# 153-01C_Mode_X_LPT_adapter.net
KiCad netlist of a schematic drawn in EAGLE
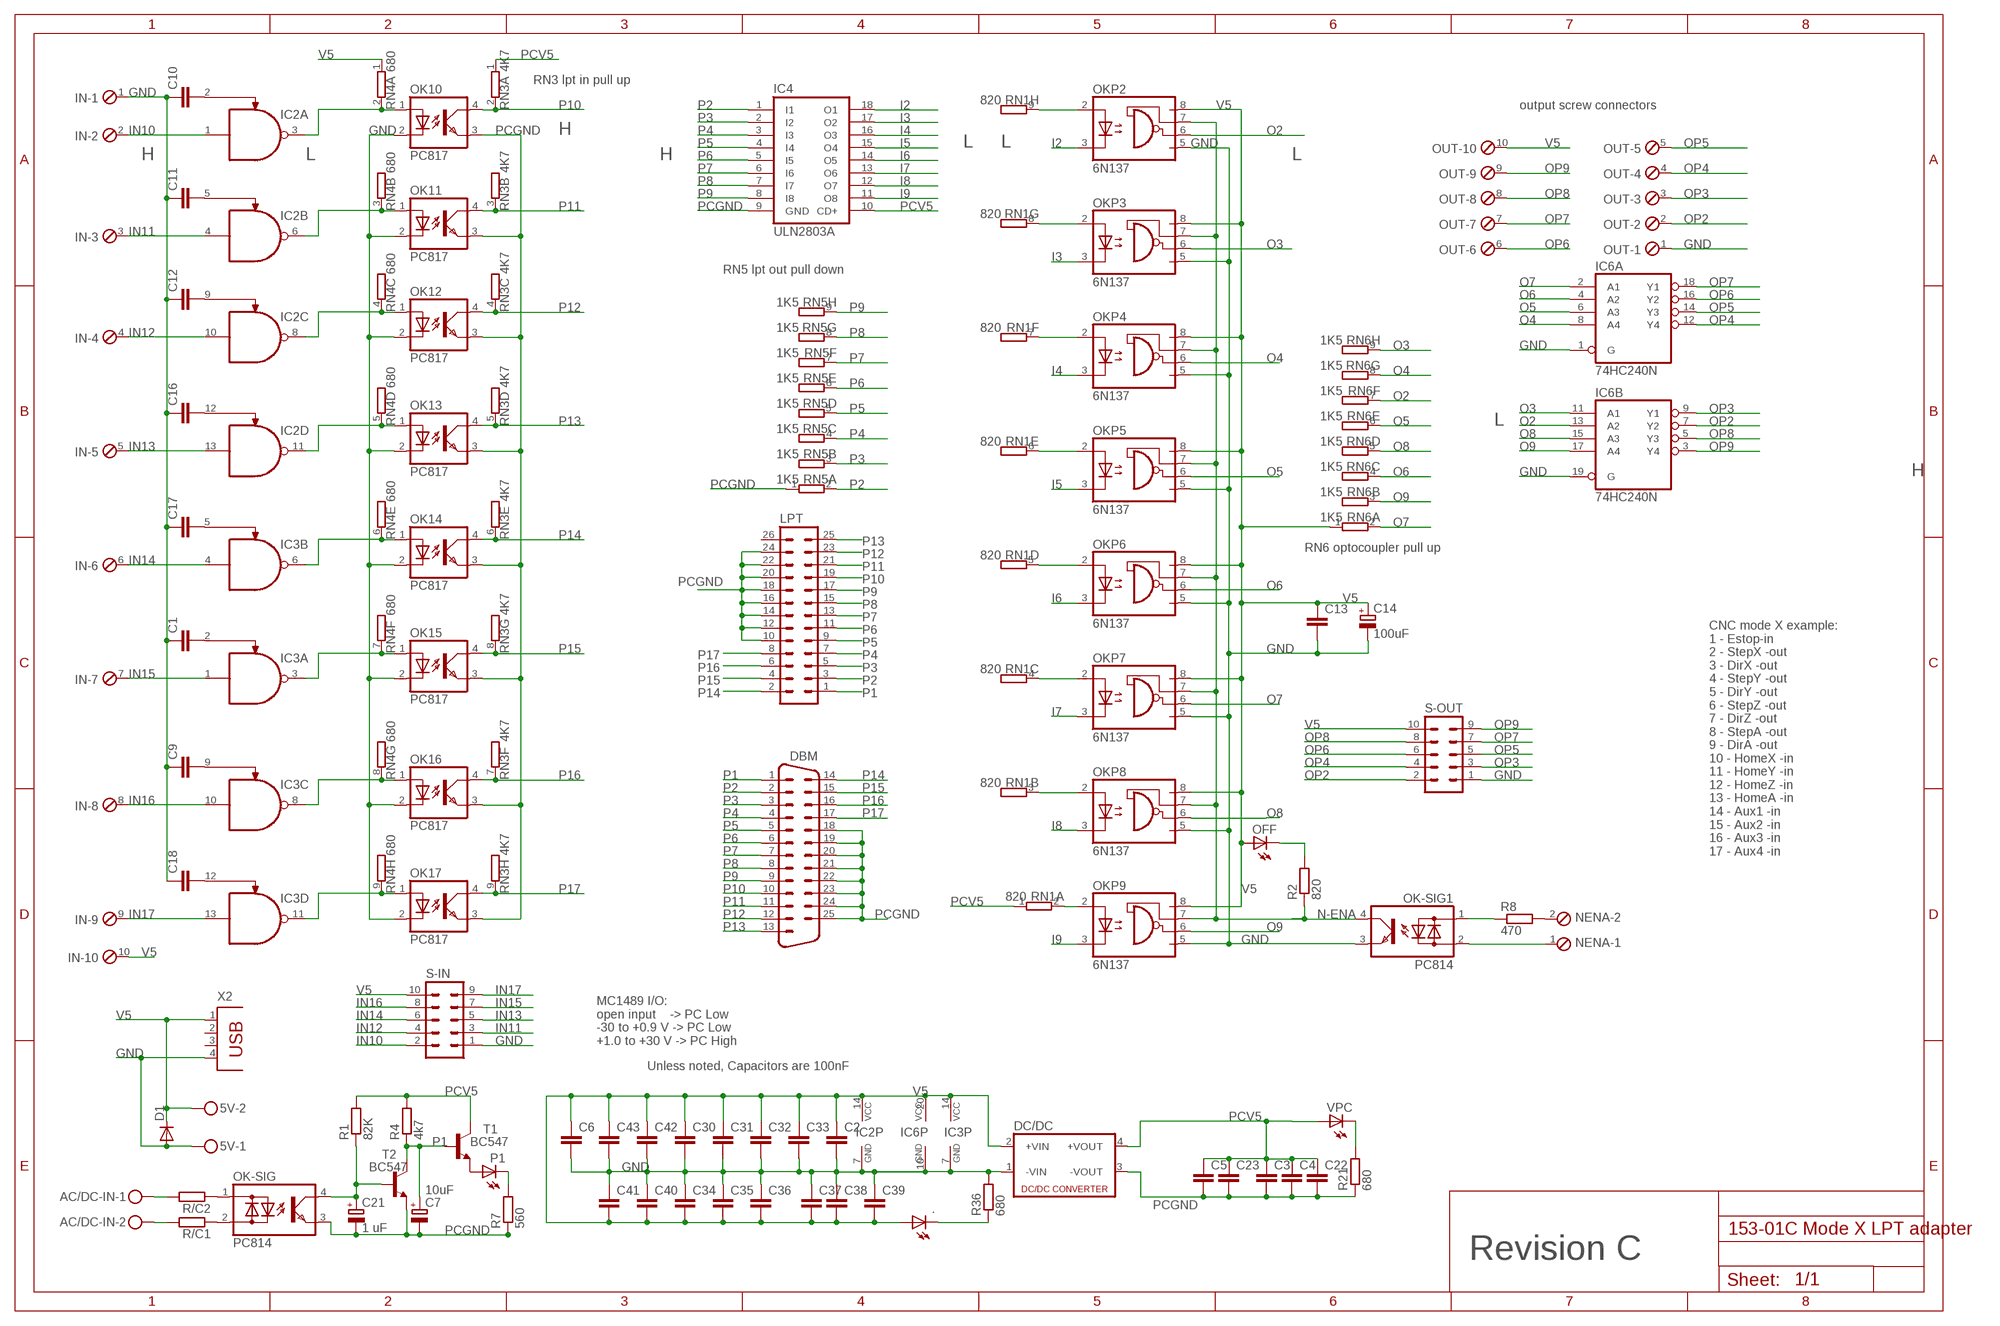
[diagram p0: schematic, sheet 1]

(export (version "E")
  (design (tool "Eeschema 10.0.6"))
  (components
    (comp (ref ".")
      (value "LED3MM")
      (footprint "eagle-import:LED3MM")
      (libsource (lib "eagle-import") (part "LED3MM"))
    )
    (comp (ref "5V")
      (value "MKDSN1,5/2-5,08")
      (footprint "eagle-import:MKDSN1,5_2-5,08")
      (libsource (lib "eagle-import") (part "MKDSN1,5/2-5,08"))
    )
    (comp (ref "AC/DC-IN")
      (value "MKDSN1,5/2-5,08")
      (footprint "eagle-import:MKDSN1,5_2-5,08")
      (libsource (lib "eagle-import") (part "MKDSN1,5/2-5,08"))
    )
    (comp (ref "C1")
      (value "C-EU025-024X044")
      (footprint "eagle-import:C025-024X044")
      (libsource (lib "eagle-import") (part "C-EU025-024X044"))
    )
    (comp (ref "C2")
      (value "C-EU025-024X044")
      (footprint "eagle-import:C025-024X044")
      (libsource (lib "eagle-import") (part "C-EU025-024X044"))
    )
    (comp (ref "C3")
      (value "C-EU025-024X044")
      (footprint "eagle-import:C025-024X044")
      (libsource (lib "eagle-import") (part "C-EU025-024X044"))
    )
    (comp (ref "C4")
      (value "C-EU025-024X044")
      (footprint "eagle-import:C025-024X044")
      (libsource (lib "eagle-import") (part "C-EU025-024X044"))
    )
    (comp (ref "C5")
      (value "C-EU025-024X044")
      (footprint "eagle-import:C025-024X044")
      (libsource (lib "eagle-import") (part "C-EU025-024X044"))
    )
    (comp (ref "C6")
      (value "C-EU025-024X044")
      (footprint "eagle-import:C025-024X044")
      (libsource (lib "eagle-import") (part "C-EU025-024X044"))
    )
    (comp (ref "C7")
      (value "10uF")
      (footprint "eagle-import:E5-6")
      (libsource (lib "eagle-import") (part "CPOL-EUE5-6"))
    )
    (comp (ref "C9")
      (value "C-EU025-024X044")
      (footprint "eagle-import:C025-024X044")
      (libsource (lib "eagle-import") (part "C-EU025-024X044"))
    )
    (comp (ref "C10")
      (value "C-EU025-024X044")
      (footprint "eagle-import:C025-024X044")
      (libsource (lib "eagle-import") (part "C-EU025-024X044"))
    )
    (comp (ref "C11")
      (value "C-EU025-024X044")
      (footprint "eagle-import:C025-024X044")
      (libsource (lib "eagle-import") (part "C-EU025-024X044"))
    )
    (comp (ref "C12")
      (value "C-EU025-024X044")
      (footprint "eagle-import:C025-024X044")
      (libsource (lib "eagle-import") (part "C-EU025-024X044"))
    )
    (comp (ref "C13")
      (value "C-EU025-024X044")
      (footprint "eagle-import:C025-024X044")
      (libsource (lib "eagle-import") (part "C-EU025-024X044"))
    )
    (comp (ref "C14")
      (value "100uF")
      (footprint "eagle-import:E3,5-8")
      (libsource (lib "eagle-import") (part "CPOL-EUE3.5-8"))
    )
    (comp (ref "C16")
      (value "C-EU025-024X044")
      (footprint "eagle-import:C025-024X044")
      (libsource (lib "eagle-import") (part "C-EU025-024X044"))
    )
    (comp (ref "C17")
      (value "C-EU025-024X044")
      (footprint "eagle-import:C025-024X044")
      (libsource (lib "eagle-import") (part "C-EU025-024X044"))
    )
    (comp (ref "C18")
      (value "C-EU025-024X044")
      (footprint "eagle-import:C025-024X044")
      (libsource (lib "eagle-import") (part "C-EU025-024X044"))
    )
    (comp (ref "C21")
      (value "1 uF")
      (footprint "eagle-import:E2,5-6")
      (libsource (lib "eagle-import") (part "CPOL-EUE2.5-6"))
    )
    (comp (ref "C22")
      (value "C-EU025-024X044")
      (footprint "eagle-import:C025-024X044")
      (libsource (lib "eagle-import") (part "C-EU025-024X044"))
    )
    (comp (ref "C23")
      (value "C-EU025-024X044")
      (footprint "eagle-import:C025-024X044")
      (libsource (lib "eagle-import") (part "C-EU025-024X044"))
    )
    (comp (ref "C30")
      (value "C-EU025-024X044")
      (footprint "eagle-import:C025-024X044")
      (libsource (lib "eagle-import") (part "C-EU025-024X044"))
    )
    (comp (ref "C31")
      (value "C-EU025-024X044")
      (footprint "eagle-import:C025-024X044")
      (libsource (lib "eagle-import") (part "C-EU025-024X044"))
    )
    (comp (ref "C32")
      (value "C-EU025-024X044")
      (footprint "eagle-import:C025-024X044")
      (libsource (lib "eagle-import") (part "C-EU025-024X044"))
    )
    (comp (ref "C33")
      (value "C-EU025-024X044")
      (footprint "eagle-import:C025-024X044")
      (libsource (lib "eagle-import") (part "C-EU025-024X044"))
    )
    (comp (ref "C34")
      (value "C-EU025-024X044")
      (footprint "eagle-import:C025-024X044")
      (libsource (lib "eagle-import") (part "C-EU025-024X044"))
    )
    (comp (ref "C35")
      (value "C-EU025-024X044")
      (footprint "eagle-import:C025-024X044")
      (libsource (lib "eagle-import") (part "C-EU025-024X044"))
    )
    (comp (ref "C36")
      (value "C-EU025-024X044")
      (footprint "eagle-import:C025-024X044")
      (libsource (lib "eagle-import") (part "C-EU025-024X044"))
    )
    (comp (ref "C37")
      (value "C-EU025-024X044")
      (footprint "eagle-import:C025-024X044")
      (libsource (lib "eagle-import") (part "C-EU025-024X044"))
    )
    (comp (ref "C38")
      (value "C-EU025-024X044")
      (footprint "eagle-import:C025-024X044")
      (libsource (lib "eagle-import") (part "C-EU025-024X044"))
    )
    (comp (ref "C39")
      (value "C-EU025-024X044")
      (footprint "eagle-import:C025-024X044")
      (libsource (lib "eagle-import") (part "C-EU025-024X044"))
    )
    (comp (ref "C40")
      (value "C-EU025-024X044")
      (footprint "eagle-import:C025-024X044")
      (libsource (lib "eagle-import") (part "C-EU025-024X044"))
    )
    (comp (ref "C41")
      (value "C-EU025-024X044")
      (footprint "eagle-import:C025-024X044")
      (libsource (lib "eagle-import") (part "C-EU025-024X044"))
    )
    (comp (ref "C42")
      (value "C-EU025-024X044")
      (footprint "eagle-import:C025-024X044")
      (libsource (lib "eagle-import") (part "C-EU025-024X044"))
    )
    (comp (ref "C43")
      (value "C-EU025-024X044")
      (footprint "eagle-import:C025-024X044")
      (libsource (lib "eagle-import") (part "C-EU025-024X044"))
    )
    (comp (ref "D1")
      (value "1N4148DO35-10")
      (footprint "eagle-import:DO35-10")
      (libsource (lib "eagle-import") (part "1N4148DO35-10"))
    )
    (comp (ref "DBM")
      (value "M25HP")
      (footprint "eagle-import:M25HP")
      (libsource (lib "eagle-import") (part "M25HP"))
    )
    (comp (ref "DC/DC")
      (value "VA-1205S")
      (footprint "eagle-import:4SIL")
      (libsource (lib "eagle-import") (part "VA-?S1205"))
    )
    (comp (ref "IC2")
      (value "MC1489DIP")
      (footprint "eagle-import:DIL14")
      (libsource (lib "eagle-import") (part "MC1489DIP"))
    )
    (comp (ref "IC3")
      (value "MC1489DIP")
      (footprint "eagle-import:DIL14")
      (libsource (lib "eagle-import") (part "MC1489DIP"))
    )
    (comp (ref "IC4")
      (value "ULN2803A")
      (footprint "eagle-import:DIL18")
      (libsource (lib "eagle-import") (part "ULN2803A"))
    )
    (comp (ref "IC6")
      (value "74HC240N")
      (footprint "eagle-import:DIL20")
      (libsource (lib "eagle-import") (part "74240NHC"))
    )
    (comp (ref "IN")
      (value "MPT10")
      (footprint "eagle-import:10POL254")
      (libsource (lib "eagle-import") (part "MPT10"))
    )
    (comp (ref "LPT")
      (value "ML26")
      (footprint "eagle-import:ML26")
      (libsource (lib "eagle-import") (part "ML26"))
    )
    (comp (ref "NENA")
      (value "MPT2")
      (footprint "eagle-import:2POL254")
      (libsource (lib "eagle-import") (part "MPT2"))
    )
    (comp (ref "OFF")
      (value "LED3MM")
      (footprint "eagle-import:LED3MM")
      (libsource (lib "eagle-import") (part "LED3MM"))
    )
    (comp (ref "OK-SIG")
      (value "PC814")
      (footprint "eagle-import:DIL04")
      (libsource (lib "eagle-import") (part "PC814"))
    )
    (comp (ref "OK-SIG1")
      (value "PC814")
      (footprint "eagle-import:DIL04")
      (libsource (lib "eagle-import") (part "PC814"))
    )
    (comp (ref "OK10")
      (value "PC817")
      (footprint "eagle-import:DIL04")
      (fields (field (name "MPN") "PC817X4J000F"))
      (libsource (lib "eagle-import") (part "PC817"))
    )
    (comp (ref "OK11")
      (value "PC817")
      (footprint "eagle-import:DIL04")
      (fields (field (name "MPN") "PC817X4J000F"))
      (libsource (lib "eagle-import") (part "PC817"))
    )
    (comp (ref "OK12")
      (value "PC817")
      (footprint "eagle-import:DIL04")
      (fields (field (name "MPN") "PC817X4J000F"))
      (libsource (lib "eagle-import") (part "PC817"))
    )
    (comp (ref "OK13")
      (value "PC817")
      (footprint "eagle-import:DIL04")
      (fields (field (name "MPN") "PC817X4J000F"))
      (libsource (lib "eagle-import") (part "PC817"))
    )
    (comp (ref "OK14")
      (value "PC817")
      (footprint "eagle-import:DIL04")
      (fields (field (name "MPN") "PC817X4J000F"))
      (libsource (lib "eagle-import") (part "PC817"))
    )
    (comp (ref "OK15")
      (value "PC817")
      (footprint "eagle-import:DIL04")
      (fields (field (name "MPN") "PC817X4J000F"))
      (libsource (lib "eagle-import") (part "PC817"))
    )
    (comp (ref "OK16")
      (value "PC817")
      (footprint "eagle-import:DIL04")
      (fields (field (name "MPN") "PC817X4J000F"))
      (libsource (lib "eagle-import") (part "PC817"))
    )
    (comp (ref "OK17")
      (value "PC817")
      (footprint "eagle-import:DIL04")
      (fields (field (name "MPN") "PC817X4J000F"))
      (libsource (lib "eagle-import") (part "PC817"))
    )
    (comp (ref "OKP2")
      (value "6N137")
      (footprint "eagle-import:DIL08")
      (libsource (lib "eagle-import") (part "6N137"))
    )
    (comp (ref "OKP3")
      (value "6N137")
      (footprint "eagle-import:DIL08")
      (libsource (lib "eagle-import") (part "6N137"))
    )
    (comp (ref "OKP4")
      (value "6N137")
      (footprint "eagle-import:DIL08")
      (libsource (lib "eagle-import") (part "6N137"))
    )
    (comp (ref "OKP5")
      (value "6N137")
      (footprint "eagle-import:DIL08")
      (libsource (lib "eagle-import") (part "6N137"))
    )
    (comp (ref "OKP6")
      (value "6N137")
      (footprint "eagle-import:DIL08")
      (libsource (lib "eagle-import") (part "6N137"))
    )
    (comp (ref "OKP7")
      (value "6N137")
      (footprint "eagle-import:DIL08")
      (libsource (lib "eagle-import") (part "6N137"))
    )
    (comp (ref "OKP8")
      (value "6N137")
      (footprint "eagle-import:DIL08")
      (libsource (lib "eagle-import") (part "6N137"))
    )
    (comp (ref "OKP9")
      (value "6N137")
      (footprint "eagle-import:DIL08")
      (libsource (lib "eagle-import") (part "6N137"))
    )
    (comp (ref "OUT")
      (value "MPT10")
      (footprint "eagle-import:10POL254")
      (libsource (lib "eagle-import") (part "MPT10"))
    )
    (comp (ref "P1")
      (value "LED3MM")
      (footprint "eagle-import:LED3MM")
      (libsource (lib "eagle-import") (part "LED3MM"))
    )
    (comp (ref "R/C1")
      (value "R-EU_0309/10")
      (footprint "eagle-import:0309_10")
      (libsource (lib "eagle-import") (part "R-EU_0309/10"))
    )
    (comp (ref "R/C2")
      (value "R-EU_0309/10")
      (footprint "eagle-import:0309_10")
      (libsource (lib "eagle-import") (part "R-EU_0309/10"))
    )
    (comp (ref "R1")
      (value "82K")
      (footprint "eagle-import:0207_10")
      (libsource (lib "eagle-import") (part "R-EU_0207/10"))
    )
    (comp (ref "R2")
      (value "820")
      (footprint "eagle-import:0207_10")
      (libsource (lib "eagle-import") (part "R-EU_0207/10"))
    )
    (comp (ref "R4")
      (value "4k7")
      (footprint "eagle-import:0207_10")
      (libsource (lib "eagle-import") (part "R-EU_0207/10"))
    )
    (comp (ref "R7")
      (value "560")
      (footprint "eagle-import:0207_10")
      (libsource (lib "eagle-import") (part "R-EU_0207/10"))
    )
    (comp (ref "R8")
      (value "470")
      (footprint "eagle-import:0207_10")
      (libsource (lib "eagle-import") (part "R-EU_0207/10"))
    )
    (comp (ref "R21")
      (value "680")
      (footprint "eagle-import:0207_10")
      (libsource (lib "eagle-import") (part "R-EU_0207/10"))
    )
    (comp (ref "R36")
      (value "680")
      (footprint "eagle-import:0207_10")
      (libsource (lib "eagle-import") (part "R-EU_0207/10"))
    )
    (comp (ref "RN1")
      (value "820")
      (footprint "eagle-import:SIL9")
      (libsource (lib "eagle-import") (part "GE08R"))
    )
    (comp (ref "RN3")
      (value "4K7")
      (footprint "eagle-import:SIL9")
      (libsource (lib "eagle-import") (part "GE08R"))
    )
    (comp (ref "RN4")
      (value "680")
      (footprint "eagle-import:SIL9")
      (libsource (lib "eagle-import") (part "GE08R"))
    )
    (comp (ref "RN5")
      (value "1K5")
      (footprint "eagle-import:SIL9")
      (libsource (lib "eagle-import") (part "GE08R"))
    )
    (comp (ref "RN6")
      (value "1K5")
      (footprint "eagle-import:SIL9")
      (libsource (lib "eagle-import") (part "GE08R"))
    )
    (comp (ref "S-IN")
      (value "ML10")
      (footprint "eagle-import:ML10")
      (libsource (lib "eagle-import") (part "ML10"))
    )
    (comp (ref "S-OUT")
      (value "ML10")
      (footprint "eagle-import:ML10")
      (libsource (lib "eagle-import") (part "ML10"))
    )
    (comp (ref "T1")
      (value "BC547")
      (footprint "eagle-import:TO92")
      (libsource (lib "eagle-import") (part "BC547"))
    )
    (comp (ref "T2")
      (value "BC547")
      (footprint "eagle-import:TO92")
      (libsource (lib "eagle-import") (part "BC547"))
    )
    (comp (ref "VPC")
      (value "LED3MM")
      (footprint "eagle-import:LED3MM")
      (libsource (lib "eagle-import") (part "LED3MM"))
    )
    (comp (ref "X2")
      (value "PN87520")
      (footprint "eagle-import:PN87520")
      (libsource (lib "eagle-import") (part "PN87520"))
    )
  )
  (nets
    (net (code "1") (name "/GND") (class "Default")
      (node (ref "5V") (pin "1") (pinfunction "KL_1") (pintype "passive"))
      (node (ref "C1") (pin "1") (pinfunction "1_1") (pintype "passive"))
      (node (ref "C10") (pin "1") (pinfunction "1_1") (pintype "passive"))
      (node (ref "C11") (pin "1") (pinfunction "1_1") (pintype "passive"))
      (node (ref "C12") (pin "1") (pinfunction "1_1") (pintype "passive"))
      (node (ref "C13") (pin "2") (pinfunction "2_2") (pintype "passive"))
      (node (ref "C14") (pin "-") (pinfunction "-_-") (pintype "passive"))
      (node (ref "C16") (pin "1") (pinfunction "1_1") (pintype "passive"))
      (node (ref "C17") (pin "1") (pinfunction "1_1") (pintype "passive"))
      (node (ref "C18") (pin "1") (pinfunction "1_1") (pintype "passive"))
      (node (ref "C2") (pin "2") (pinfunction "2_2") (pintype "passive"))
      (node (ref "C30") (pin "2") (pinfunction "2_2") (pintype "passive"))
      (node (ref "C31") (pin "2") (pinfunction "2_2") (pintype "passive"))
      (node (ref "C32") (pin "2") (pinfunction "2_2") (pintype "passive"))
      (node (ref "C33") (pin "2") (pinfunction "2_2") (pintype "passive"))
      (node (ref "C34") (pin "1") (pinfunction "1_1") (pintype "passive"))
      (node (ref "C35") (pin "1") (pinfunction "1_1") (pintype "passive"))
      (node (ref "C36") (pin "1") (pinfunction "1_1") (pintype "passive"))
      (node (ref "C37") (pin "1") (pinfunction "1_1") (pintype "passive"))
      (node (ref "C38") (pin "1") (pinfunction "1_1") (pintype "passive"))
      (node (ref "C39") (pin "1") (pinfunction "1_1") (pintype "passive"))
      (node (ref "C40") (pin "1") (pinfunction "1_1") (pintype "passive"))
      (node (ref "C41") (pin "1") (pinfunction "1_1") (pintype "passive"))
      (node (ref "C42") (pin "2") (pinfunction "2_2") (pintype "passive"))
      (node (ref "C43") (pin "2") (pinfunction "2_2") (pintype "passive"))
      (node (ref "C6") (pin "2") (pinfunction "2_2") (pintype "passive"))
      (node (ref "C9") (pin "1") (pinfunction "1_1") (pintype "passive"))
      (node (ref "D1") (pin "A") (pinfunction "A_A") (pintype "passive"))
      (node (ref "DC/DC") (pin "1") (pinfunction "-VIN_1") (pintype "passive"))
      (node (ref "IC2") (pin "7") (pinfunction "GND_7") (pintype "power_in"))
      (node (ref "IC3") (pin "7") (pinfunction "GND_7") (pintype "power_in"))
      (node (ref "IC6") (pin "1") (pinfunction "G_1") (pintype "input"))
      (node (ref "IC6") (pin "10") (pinfunction "GND_10") (pintype "power_in"))
      (node (ref "IC6") (pin "19") (pinfunction "G_19") (pintype "input"))
      (node (ref "IN") (pin "1") (pinfunction "1_1") (pintype "passive"))
      (node (ref "OK-SIG1") (pin "3") (pinfunction "E_3") (pintype "passive"))
      (node (ref "OK10") (pin "2") (pinfunction "C_2") (pintype "passive"))
      (node (ref "OK11") (pin "2") (pinfunction "C_2") (pintype "passive"))
      (node (ref "OK12") (pin "2") (pinfunction "C_2") (pintype "passive"))
      (node (ref "OK13") (pin "2") (pinfunction "C_2") (pintype "passive"))
      (node (ref "OK14") (pin "2") (pinfunction "C_2") (pintype "passive"))
      (node (ref "OK15") (pin "2") (pinfunction "C_2") (pintype "passive"))
      (node (ref "OK16") (pin "2") (pinfunction "C_2") (pintype "passive"))
      (node (ref "OK17") (pin "2") (pinfunction "C_2") (pintype "passive"))
      (node (ref "OKP2") (pin "5") (pinfunction "GND_5") (pintype "passive"))
      (node (ref "OKP3") (pin "5") (pinfunction "GND_5") (pintype "passive"))
      (node (ref "OKP4") (pin "5") (pinfunction "GND_5") (pintype "passive"))
      (node (ref "OKP5") (pin "5") (pinfunction "GND_5") (pintype "passive"))
      (node (ref "OKP6") (pin "5") (pinfunction "GND_5") (pintype "passive"))
      (node (ref "OKP7") (pin "5") (pinfunction "GND_5") (pintype "passive"))
      (node (ref "OKP8") (pin "5") (pinfunction "GND_5") (pintype "passive"))
      (node (ref "OKP9") (pin "5") (pinfunction "GND_5") (pintype "passive"))
      (node (ref "OUT") (pin "1") (pinfunction "1_1") (pintype "passive"))
      (node (ref "R36") (pin "2") (pinfunction "2_2") (pintype "passive"))
      (node (ref "S-IN") (pin "1") (pinfunction "1_1") (pintype "passive"))
      (node (ref "S-OUT") (pin "1") (pinfunction "1_1") (pintype "passive"))
      (node (ref "X2") (pin "4") (pinfunction "4_4") (pintype "passive"))
    )
    (net (code "2") (name "/I2") (class "Default")
      (node (ref "IC4") (pin "18") (pinfunction "O1_18") (pintype "open_collector"))
      (node (ref "OKP2") (pin "3") (pinfunction "C_3") (pintype "passive"))
    )
    (net (code "3") (name "/I3") (class "Default")
      (node (ref "IC4") (pin "17") (pinfunction "O2_17") (pintype "open_collector"))
      (node (ref "OKP3") (pin "3") (pinfunction "C_3") (pintype "passive"))
    )
    (net (code "4") (name "/I4") (class "Default")
      (node (ref "IC4") (pin "16") (pinfunction "O3_16") (pintype "open_collector"))
      (node (ref "OKP4") (pin "3") (pinfunction "C_3") (pintype "passive"))
    )
    (net (code "5") (name "/I5") (class "Default")
      (node (ref "IC4") (pin "15") (pinfunction "O4_15") (pintype "open_collector"))
      (node (ref "OKP5") (pin "3") (pinfunction "C_3") (pintype "passive"))
    )
    (net (code "6") (name "/I6") (class "Default")
      (node (ref "IC4") (pin "14") (pinfunction "O5_14") (pintype "open_collector"))
      (node (ref "OKP6") (pin "3") (pinfunction "C_3") (pintype "passive"))
    )
    (net (code "7") (name "/I7") (class "Default")
      (node (ref "IC4") (pin "13") (pinfunction "O6_13") (pintype "open_collector"))
      (node (ref "OKP7") (pin "3") (pinfunction "C_3") (pintype "passive"))
    )
    (net (code "8") (name "/I8") (class "Default")
      (node (ref "IC4") (pin "12") (pinfunction "O7_12") (pintype "open_collector"))
      (node (ref "OKP8") (pin "3") (pinfunction "C_3") (pintype "passive"))
    )
    (net (code "9") (name "/I9") (class "Default")
      (node (ref "IC4") (pin "11") (pinfunction "O8_11") (pintype "open_collector"))
      (node (ref "OKP9") (pin "3") (pinfunction "C_3") (pintype "passive"))
    )
    (net (code "10") (name "/IN10") (class "Default")
      (node (ref "IC2") (pin "1") (pinfunction "I0_1") (pintype "input"))
      (node (ref "IN") (pin "2") (pinfunction "1_2") (pintype "passive"))
      (node (ref "S-IN") (pin "2") (pinfunction "2_2") (pintype "passive"))
    )
    (net (code "11") (name "/IN11") (class "Default")
      (node (ref "IC2") (pin "4") (pinfunction "I0_4") (pintype "input"))
      (node (ref "IN") (pin "3") (pinfunction "1_3") (pintype "passive"))
      (node (ref "S-IN") (pin "3") (pinfunction "3_3") (pintype "passive"))
    )
    (net (code "12") (name "/IN12") (class "Default")
      (node (ref "IC2") (pin "10") (pinfunction "I0_10") (pintype "input"))
      (node (ref "IN") (pin "4") (pinfunction "1_4") (pintype "passive"))
      (node (ref "S-IN") (pin "4") (pinfunction "4_4") (pintype "passive"))
    )
    (net (code "13") (name "/IN13") (class "Default")
      (node (ref "IC2") (pin "13") (pinfunction "I0_13") (pintype "input"))
      (node (ref "IN") (pin "5") (pinfunction "1_5") (pintype "passive"))
      (node (ref "S-IN") (pin "5") (pinfunction "5_5") (pintype "passive"))
    )
    (net (code "14") (name "/IN14") (class "Default")
      (node (ref "IC3") (pin "4") (pinfunction "I0_4") (pintype "input"))
      (node (ref "IN") (pin "6") (pinfunction "1_6") (pintype "passive"))
      (node (ref "S-IN") (pin "6") (pinfunction "6_6") (pintype "passive"))
    )
    (net (code "15") (name "/IN15") (class "Default")
      (node (ref "IC3") (pin "1") (pinfunction "I0_1") (pintype "input"))
      (node (ref "IN") (pin "7") (pinfunction "1_7") (pintype "passive"))
      (node (ref "S-IN") (pin "7") (pinfunction "7_7") (pintype "passive"))
    )
    (net (code "16") (name "/IN16") (class "Default")
      (node (ref "IC3") (pin "10") (pinfunction "I0_10") (pintype "input"))
      (node (ref "IN") (pin "8") (pinfunction "1_8") (pintype "passive"))
      (node (ref "S-IN") (pin "8") (pinfunction "8_8") (pintype "passive"))
    )
    (net (code "17") (name "/IN17") (class "Default")
      (node (ref "IC3") (pin "13") (pinfunction "I0_13") (pintype "input"))
      (node (ref "IN") (pin "9") (pinfunction "1_9") (pintype "passive"))
      (node (ref "S-IN") (pin "9") (pinfunction "9_9") (pintype "passive"))
    )
    (net (code "18") (name "/N-ENA") (class "Default")
      (node (ref "OK-SIG1") (pin "4") (pinfunction "C_4") (pintype "passive"))
      (node (ref "OKP2") (pin "7") (pinfunction "VE_7") (pintype "passive"))
      (node (ref "OKP3") (pin "7") (pinfunction "VE_7") (pintype "passive"))
      (node (ref "OKP4") (pin "7") (pinfunction "VE_7") (pintype "passive"))
      (node (ref "OKP5") (pin "7") (pinfunction "VE_7") (pintype "passive"))
      (node (ref "OKP6") (pin "7") (pinfunction "VE_7") (pintype "passive"))
      (node (ref "OKP7") (pin "7") (pinfunction "VE_7") (pintype "passive"))
      (node (ref "OKP8") (pin "7") (pinfunction "VE_7") (pintype "passive"))
      (node (ref "OKP9") (pin "7") (pinfunction "VE_7") (pintype "passive"))
      (node (ref "R2") (pin "1") (pinfunction "1_1") (pintype "passive"))
    )
    (net (code "19") (name "/O2") (class "Default")
      (node (ref "IC6") (pin "13") (pinfunction "A2_13") (pintype "input"))
      (node (ref "OKP2") (pin "6") (pinfunction "VO_6") (pintype "passive"))
      (node (ref "RN6") (pin "7") (pinfunction "2_7") (pintype "passive"))
    )
    (net (code "20") (name "/O3") (class "Default")
      (node (ref "IC6") (pin "11") (pinfunction "A1_11") (pintype "input"))
      (node (ref "OKP3") (pin "6") (pinfunction "VO_6") (pintype "passive"))
      (node (ref "RN6") (pin "9") (pinfunction "2_9") (pintype "passive"))
    )
    (net (code "21") (name "/O4") (class "Default")
      (node (ref "IC6") (pin "8") (pinfunction "A4_8") (pintype "input"))
      (node (ref "OKP4") (pin "6") (pinfunction "VO_6") (pintype "passive"))
      (node (ref "RN6") (pin "8") (pinfunction "2_8") (pintype "passive"))
    )
    (net (code "22") (name "/O5") (class "Default")
      (node (ref "IC6") (pin "6") (pinfunction "A3_6") (pintype "input"))
      (node (ref "OKP5") (pin "6") (pinfunction "VO_6") (pintype "passive"))
      (node (ref "RN6") (pin "6") (pinfunction "2_6") (pintype "passive"))
    )
    (net (code "23") (name "/O6") (class "Default")
      (node (ref "IC6") (pin "4") (pinfunction "A2_4") (pintype "input"))
      (node (ref "OKP6") (pin "6") (pinfunction "VO_6") (pintype "passive"))
      (node (ref "RN6") (pin "4") (pinfunction "2_4") (pintype "passive"))
    )
    (net (code "24") (name "/O7") (class "Default")
      (node (ref "IC6") (pin "2") (pinfunction "A1_2") (pintype "input"))
      (node (ref "OKP7") (pin "6") (pinfunction "VO_6") (pintype "passive"))
      (node (ref "RN6") (pin "2") (pinfunction "2_2") (pintype "passive"))
    )
    (net (code "25") (name "/O8") (class "Default")
      (node (ref "IC6") (pin "15") (pinfunction "A3_15") (pintype "input"))
      (node (ref "OKP8") (pin "6") (pinfunction "VO_6") (pintype "passive"))
      (node (ref "RN6") (pin "5") (pinfunction "2_5") (pintype "passive"))
    )
    (net (code "26") (name "/O9") (class "Default")
      (node (ref "IC6") (pin "17") (pinfunction "A4_17") (pintype "input"))
      (node (ref "OKP9") (pin "6") (pinfunction "VO_6") (pintype "passive"))
      (node (ref "RN6") (pin "3") (pinfunction "2_3") (pintype "passive"))
    )
    (net (code "27") (name "/OP2") (class "Default")
      (node (ref "IC6") (pin "7") (pinfunction "Y2_7") (pintype "tri_state"))
      (node (ref "OUT") (pin "2") (pinfunction "1_2") (pintype "passive"))
      (node (ref "S-OUT") (pin "2") (pinfunction "2_2") (pintype "passive"))
    )
    (net (code "28") (name "/OP3") (class "Default")
      (node (ref "IC6") (pin "9") (pinfunction "Y1_9") (pintype "tri_state"))
      (node (ref "OUT") (pin "3") (pinfunction "1_3") (pintype "passive"))
      (node (ref "S-OUT") (pin "3") (pinfunction "3_3") (pintype "passive"))
    )
    (net (code "29") (name "/OP4") (class "Default")
      (node (ref "IC6") (pin "12") (pinfunction "Y4_12") (pintype "tri_state"))
      (node (ref "OUT") (pin "4") (pinfunction "1_4") (pintype "passive"))
      (node (ref "S-OUT") (pin "4") (pinfunction "4_4") (pintype "passive"))
    )
    (net (code "30") (name "/OP5") (class "Default")
      (node (ref "IC6") (pin "14") (pinfunction "Y3_14") (pintype "tri_state"))
      (node (ref "OUT") (pin "5") (pinfunction "1_5") (pintype "passive"))
      (node (ref "S-OUT") (pin "5") (pinfunction "5_5") (pintype "passive"))
    )
    (net (code "31") (name "/OP6") (class "Default")
      (node (ref "IC6") (pin "16") (pinfunction "Y2_16") (pintype "tri_state"))
      (node (ref "OUT") (pin "6") (pinfunction "1_6") (pintype "passive"))
      (node (ref "S-OUT") (pin "6") (pinfunction "6_6") (pintype "passive"))
    )
    (net (code "32") (name "/OP7") (class "Default")
      (node (ref "IC6") (pin "18") (pinfunction "Y1_18") (pintype "tri_state"))
      (node (ref "OUT") (pin "7") (pinfunction "1_7") (pintype "passive"))
      (node (ref "S-OUT") (pin "7") (pinfunction "7_7") (pintype "passive"))
    )
    (net (code "33") (name "/OP8") (class "Default")
      (node (ref "IC6") (pin "5") (pinfunction "Y3_5") (pintype "tri_state"))
      (node (ref "OUT") (pin "8") (pinfunction "1_8") (pintype "passive"))
      (node (ref "S-OUT") (pin "8") (pinfunction "8_8") (pintype "passive"))
    )
    (net (code "34") (name "/OP9") (class "Default")
      (node (ref "IC6") (pin "3") (pinfunction "Y4_3") (pintype "tri_state"))
      (node (ref "OUT") (pin "9") (pinfunction "1_9") (pintype "passive"))
      (node (ref "S-OUT") (pin "9") (pinfunction "9_9") (pintype "passive"))
    )
    (net (code "35") (name "/P1") (class "Default")
      (node (ref "C7") (pin "+") (pinfunction "+_+") (pintype "passive"))
      (node (ref "DBM") (pin "1") (pinfunction "1_1") (pintype "passive"))
      (node (ref "LPT") (pin "1") (pinfunction "1_1") (pintype "passive"))
      (node (ref "R4") (pin "1") (pinfunction "1_1") (pintype "passive"))
      (node (ref "T1") (pin "2") (pinfunction "B_2") (pintype "passive"))
      (node (ref "T2") (pin "3") (pinfunction "C_3") (pintype "passive"))
    )
    (net (code "36") (name "/P2") (class "Default")
      (node (ref "DBM") (pin "2") (pinfunction "2_2") (pintype "passive"))
      (node (ref "IC4") (pin "1") (pinfunction "I1_1") (pintype "input"))
      (node (ref "LPT") (pin "3") (pinfunction "3_3") (pintype "passive"))
      (node (ref "RN5") (pin "2") (pinfunction "2_2") (pintype "passive"))
    )
    (net (code "37") (name "/P3") (class "Default")
      (node (ref "DBM") (pin "3") (pinfunction "3_3") (pintype "passive"))
      (node (ref "IC4") (pin "2") (pinfunction "I2_2") (pintype "input"))
      (node (ref "LPT") (pin "5") (pinfunction "5_5") (pintype "passive"))
      (node (ref "RN5") (pin "3") (pinfunction "2_3") (pintype "passive"))
    )
    (net (code "38") (name "/P4") (class "Default")
      (node (ref "DBM") (pin "4") (pinfunction "4_4") (pintype "passive"))
      (node (ref "IC4") (pin "3") (pinfunction "I3_3") (pintype "input"))
      (node (ref "LPT") (pin "7") (pinfunction "7_7") (pintype "passive"))
      (node (ref "RN5") (pin "4") (pinfunction "2_4") (pintype "passive"))
    )
    (net (code "39") (name "/P5") (class "Default")
      (node (ref "DBM") (pin "5") (pinfunction "5_5") (pintype "passive"))
      (node (ref "IC4") (pin "4") (pinfunction "I4_4") (pintype "input"))
      (node (ref "LPT") (pin "9") (pinfunction "9_9") (pintype "passive"))
      (node (ref "RN5") (pin "5") (pinfunction "2_5") (pintype "passive"))
    )
    (net (code "40") (name "/P6") (class "Default")
      (node (ref "DBM") (pin "6") (pinfunction "6_6") (pintype "passive"))
      (node (ref "IC4") (pin "5") (pinfunction "I5_5") (pintype "input"))
      (node (ref "LPT") (pin "11") (pinfunction "11_11") (pintype "passive"))
      (node (ref "RN5") (pin "6") (pinfunction "2_6") (pintype "passive"))
    )
    (net (code "41") (name "/P7") (class "Default")
      (node (ref "DBM") (pin "7") (pinfunction "7_7") (pintype "passive"))
      (node (ref "IC4") (pin "6") (pinfunction "I6_6") (pintype "input"))
      (node (ref "LPT") (pin "13") (pinfunction "13_13") (pintype "passive"))
      (node (ref "RN5") (pin "7") (pinfunction "2_7") (pintype "passive"))
    )
    (net (code "42") (name "/P8") (class "Default")
      (node (ref "DBM") (pin "8") (pinfunction "8_8") (pintype "passive"))
      (node (ref "IC4") (pin "7") (pinfunction "I7_7") (pintype "input"))
      (node (ref "LPT") (pin "15") (pinfunction "15_15") (pintype "passive"))
      (node (ref "RN5") (pin "8") (pinfunction "2_8") (pintype "passive"))
    )
    (net (code "43") (name "/P9") (class "Default")
      (node (ref "DBM") (pin "9") (pinfunction "9_9") (pintype "passive"))
      (node (ref "IC4") (pin "8") (pinfunction "I8_8") (pintype "input"))
      (node (ref "LPT") (pin "17") (pinfunction "17_17") (pintype "passive"))
      (node (ref "RN5") (pin "9") (pinfunction "2_9") (pintype "passive"))
    )
    (net (code "44") (name "/P10") (class "Default")
      (node (ref "DBM") (pin "10") (pinfunction "10_10") (pintype "passive"))
      (node (ref "LPT") (pin "19") (pinfunction "19_19") (pintype "passive"))
      (node (ref "OK10") (pin "4") (pinfunction "COL_4") (pintype "passive"))
      (node (ref "RN3") (pin "2") (pinfunction "2_2") (pintype "passive"))
    )
    (net (code "45") (name "/P11") (class "Default")
      (node (ref "DBM") (pin "11") (pinfunction "11_11") (pintype "passive"))
      (node (ref "LPT") (pin "21") (pinfunction "21_21") (pintype "passive"))
      (node (ref "OK11") (pin "4") (pinfunction "COL_4") (pintype "passive"))
      (node (ref "RN3") (pin "3") (pinfunction "2_3") (pintype "passive"))
    )
    (net (code "46") (name "/P12") (class "Default")
      (node (ref "DBM") (pin "12") (pinfunction "12_12") (pintype "passive"))
      (node (ref "LPT") (pin "23") (pinfunction "23_23") (pintype "passive"))
      (node (ref "OK12") (pin "4") (pinfunction "COL_4") (pintype "passive"))
      (node (ref "RN3") (pin "4") (pinfunction "2_4") (pintype "passive"))
    )
    (net (code "47") (name "/P13") (class "Default")
      (node (ref "DBM") (pin "13") (pinfunction "13_13") (pintype "passive"))
      (node (ref "LPT") (pin "25") (pinfunction "25_25") (pintype "passive"))
      (node (ref "OK13") (pin "4") (pinfunction "COL_4") (pintype "passive"))
      (node (ref "RN3") (pin "5") (pinfunction "2_5") (pintype "passive"))
    )
    (net (code "48") (name "/P14") (class "Default")
      (node (ref "DBM") (pin "14") (pinfunction "14_14") (pintype "passive"))
      (node (ref "LPT") (pin "2") (pinfunction "2_2") (pintype "passive"))
      (node (ref "OK14") (pin "4") (pinfunction "COL_4") (pintype "passive"))
      (node (ref "RN3") (pin "6") (pinfunction "2_6") (pintype "passive"))
    )
    (net (code "49") (name "/P15") (class "Default")
      (node (ref "DBM") (pin "15") (pinfunction "15_15") (pintype "passive"))
      (node (ref "LPT") (pin "4") (pinfunction "4_4") (pintype "passive"))
      (node (ref "OK15") (pin "4") (pinfunction "COL_4") (pintype "passive"))
      (node (ref "RN3") (pin "8") (pinfunction "2_8") (pintype "passive"))
    )
    (net (code "50") (name "/P16") (class "Default")
      (node (ref "DBM") (pin "16") (pinfunction "16_16") (pintype "passive"))
      (node (ref "LPT") (pin "6") (pinfunction "6_6") (pintype "passive"))
      (node (ref "OK16") (pin "4") (pinfunction "COL_4") (pintype "passive"))
      (node (ref "RN3") (pin "7") (pinfunction "2_7") (pintype "passive"))
    )
    (net (code "51") (name "/P17") (class "Default")
      (node (ref "DBM") (pin "17") (pinfunction "17_17") (pintype "passive"))
      (node (ref "LPT") (pin "8") (pinfunction "8_8") (pintype "passive"))
      (node (ref "OK17") (pin "4") (pinfunction "COL_4") (pintype "passive"))
      (node (ref "RN3") (pin "9") (pinfunction "2_9") (pintype "passive"))
    )
    (net (code "52") (name "/PCGND") (class "Default")
      (node (ref "C21") (pin "-") (pinfunction "-_-") (pintype "passive"))
      (node (ref "C22") (pin "2") (pinfunction "2_2") (pintype "passive"))
      (node (ref "C23") (pin "2") (pinfunction "2_2") (pintype "passive"))
      (node (ref "C3") (pin "2") (pinfunction "2_2") (pintype "passive"))
      (node (ref "C4") (pin "2") (pinfunction "2_2") (pintype "passive"))
      (node (ref "C5") (pin "2") (pinfunction "2_2") (pintype "passive"))
      (node (ref "C7") (pin "-") (pinfunction "-_-") (pintype "passive"))
      (node (ref "DBM") (pin "18") (pinfunction "18_18") (pintype "passive"))
      (node (ref "DBM") (pin "19") (pinfunction "19_19") (pintype "passive"))
      (node (ref "DBM") (pin "20") (pinfunction "20_20") (pintype "passive"))
      (node (ref "DBM") (pin "21") (pinfunction "21_21") (pintype "passive"))
      (node (ref "DBM") (pin "22") (pinfunction "22_22") (pintype "passive"))
      (node (ref "DBM") (pin "23") (pinfunction "23_23") (pintype "passive"))
      (node (ref "DBM") (pin "24") (pinfunction "24_24") (pintype "passive"))
      (node (ref "DBM") (pin "25") (pinfunction "25_25") (pintype "passive"))
      (node (ref "DC/DC") (pin "3") (pinfunction "-VOUT_3") (pintype "passive"))
      (node (ref "IC4") (pin "9") (pinfunction "GND_9") (pintype "power_in"))
      (node (ref "LPT") (pin "10") (pinfunction "10_10") (pintype "passive"))
      (node (ref "LPT") (pin "12") (pinfunction "12_12") (pintype "passive"))
      (node (ref "LPT") (pin "14") (pinfunction "14_14") (pintype "passive"))
      (node (ref "LPT") (pin "16") (pinfunction "16_16") (pintype "passive"))
      (node (ref "LPT") (pin "18") (pinfunction "18_18") (pintype "passive"))
      (node (ref "LPT") (pin "20") (pinfunction "20_20") (pintype "passive"))
      (node (ref "LPT") (pin "22") (pinfunction "22_22") (pintype "passive"))
      (node (ref "LPT") (pin "24") (pinfunction "24_24") (pintype "passive"))
      (node (ref "OK-SIG") (pin "3") (pinfunction "E_3") (pintype "passive"))
      (node (ref "OK10") (pin "3") (pinfunction "EMIT_3") (pintype "passive"))
      (node (ref "OK11") (pin "3") (pinfunction "EMIT_3") (pintype "passive"))
      (node (ref "OK12") (pin "3") (pinfunction "EMIT_3") (pintype "passive"))
      (node (ref "OK13") (pin "3") (pinfunction "EMIT_3") (pintype "passive"))
      (node (ref "OK14") (pin "3") (pinfunction "EMIT_3") (pintype "passive"))
      (node (ref "OK15") (pin "3") (pinfunction "EMIT_3") (pintype "passive"))
      (node (ref "OK16") (pin "3") (pinfunction "EMIT_3") (pintype "passive"))
      (node (ref "OK17") (pin "3") (pinfunction "EMIT_3") (pintype "passive"))
      (node (ref "R21") (pin "1") (pinfunction "1_1") (pintype "passive"))
      (node (ref "R7") (pin "1") (pinfunction "1_1") (pintype "passive"))
      (node (ref "RN5") (pin "1") (pinfunction "1_1") (pintype "passive"))
      (node (ref "T2") (pin "1") (pinfunction "E_1") (pintype "passive"))
    )
    (net (code "53") (name "/PCV5") (class "Default")
      (node (ref "C22") (pin "1") (pinfunction "1_1") (pintype "passive"))
      (node (ref "C23") (pin "1") (pinfunction "1_1") (pintype "passive"))
      (node (ref "C3") (pin "1") (pinfunction "1_1") (pintype "passive"))
      (node (ref "C4") (pin "1") (pinfunction "1_1") (pintype "passive"))
      (node (ref "C5") (pin "1") (pinfunction "1_1") (pintype "passive"))
      (node (ref "DC/DC") (pin "4") (pinfunction "+VOUT_4") (pintype "passive"))
      (node (ref "IC4") (pin "10") (pinfunction "CD+_10") (pintype "passive"))
      (node (ref "R1") (pin "2") (pinfunction "2_2") (pintype "passive"))
      (node (ref "R4") (pin "2") (pinfunction "2_2") (pintype "passive"))
      (node (ref "RN1") (pin "1") (pinfunction "1_1") (pintype "passive"))
      (node (ref "RN3") (pin "1") (pinfunction "1_1") (pintype "passive"))
      (node (ref "T1") (pin "3") (pinfunction "C_3") (pintype "passive"))
      (node (ref "VPC") (pin "A") (pinfunction "A_A") (pintype "passive"))
    )
    (net (code "54") (name "/V5") (class "Default")
      (node (ref ".") (pin "A") (pinfunction "A_A") (pintype "passive"))
      (node (ref "5V") (pin "2") (pinfunction "KL_2") (pintype "passive"))
      (node (ref "C13") (pin "1") (pinfunction "1_1") (pintype "passive"))
      (node (ref "C14") (pin "+") (pinfunction "+_+") (pintype "passive"))
      (node (ref "C2") (pin "1") (pinfunction "1_1") (pintype "passive"))
      (node (ref "C30") (pin "1") (pinfunction "1_1") (pintype "passive"))
      (node (ref "C31") (pin "1") (pinfunction "1_1") (pintype "passive"))
      (node (ref "C32") (pin "1") (pinfunction "1_1") (pintype "passive"))
      (node (ref "C33") (pin "1") (pinfunction "1_1") (pintype "passive"))
      (node (ref "C34") (pin "2") (pinfunction "2_2") (pintype "passive"))
      (node (ref "C35") (pin "2") (pinfunction "2_2") (pintype "passive"))
      (node (ref "C36") (pin "2") (pinfunction "2_2") (pintype "passive"))
      (node (ref "C37") (pin "2") (pinfunction "2_2") (pintype "passive"))
      (node (ref "C38") (pin "2") (pinfunction "2_2") (pintype "passive"))
      (node (ref "C39") (pin "2") (pinfunction "2_2") (pintype "passive"))
      (node (ref "C40") (pin "2") (pinfunction "2_2") (pintype "passive"))
      (node (ref "C41") (pin "2") (pinfunction "2_2") (pintype "passive"))
      (node (ref "C42") (pin "1") (pinfunction "1_1") (pintype "passive"))
      (node (ref "C43") (pin "1") (pinfunction "1_1") (pintype "passive"))
      (node (ref "C6") (pin "1") (pinfunction "1_1") (pintype "passive"))
      (node (ref "D1") (pin "C") (pinfunction "C_C") (pintype "passive"))
      (node (ref "DC/DC") (pin "2") (pinfunction "+VIN_2") (pintype "passive"))
      (node (ref "IC2") (pin "14") (pinfunction "VCC_14") (pintype "power_in"))
      (node (ref "IC3") (pin "14") (pinfunction "VCC_14") (pintype "power_in"))
      (node (ref "IC6") (pin "20") (pinfunction "VCC_20") (pintype "power_in"))
      (node (ref "IN") (pin "10") (pinfunction "1_10") (pintype "passive"))
      (node (ref "OFF") (pin "A") (pinfunction "A_A") (pintype "passive"))
      (node (ref "OKP2") (pin "8") (pinfunction "VCC_8") (pintype "passive"))
      (node (ref "OKP3") (pin "8") (pinfunction "VCC_8") (pintype "passive"))
      (node (ref "OKP4") (pin "8") (pinfunction "VCC_8") (pintype "passive"))
      (node (ref "OKP5") (pin "8") (pinfunction "VCC_8") (pintype "passive"))
      (node (ref "OKP6") (pin "8") (pinfunction "VCC_8") (pintype "passive"))
      (node (ref "OKP7") (pin "8") (pinfunction "VCC_8") (pintype "passive"))
      (node (ref "OKP8") (pin "8") (pinfunction "VCC_8") (pintype "passive"))
      (node (ref "OKP9") (pin "8") (pinfunction "VCC_8") (pintype "passive"))
      (node (ref "OUT") (pin "10") (pinfunction "1_10") (pintype "passive"))
      (node (ref "RN4") (pin "1") (pinfunction "1_1") (pintype "passive"))
      (node (ref "RN6") (pin "1") (pinfunction "1_1") (pintype "passive"))
      (node (ref "S-IN") (pin "10") (pinfunction "10_10") (pintype "passive"))
      (node (ref "S-OUT") (pin "10") (pinfunction "10_10") (pintype "passive"))
      (node (ref "X2") (pin "1") (pinfunction "1_1") (pintype "passive"))
    )
    (net (code "55") (name "Net-(.-C)") (class "Default")
      (node (ref ".") (pin "K") (pinfunction "C_K") (pintype "passive"))
      (node (ref "R36") (pin "1") (pinfunction "1_1") (pintype "passive"))
    )
    (net (code "56") (name "Net-(AC/DC-INA-KL)") (class "Default")
      (node (ref "AC/DC-IN") (pin "1") (pinfunction "KL_1") (pintype "passive"))
      (node (ref "R/C2") (pin "2") (pinfunction "2_2") (pintype "passive"))
    )
    (net (code "57") (name "Net-(AC/DC-INB-KL)") (class "Default")
      (node (ref "AC/DC-IN") (pin "2") (pinfunction "KL_2") (pintype "passive"))
      (node (ref "R/C1") (pin "2") (pinfunction "2_2") (pintype "passive"))
    )
    (net (code "58") (name "Net-(IC2A-I1)") (class "Default")
      (node (ref "C10") (pin "2") (pinfunction "2_2") (pintype "passive"))
      (node (ref "IC2") (pin "2") (pinfunction "I1_2") (pintype "input"))
    )
    (net (code "59") (name "Net-(IC2A-O)") (class "Default")
      (node (ref "IC2") (pin "3") (pinfunction "O_3") (pintype "output"))
      (node (ref "OK10") (pin "1") (pinfunction "A_1") (pintype "passive"))
      (node (ref "RN4") (pin "2") (pinfunction "2_2") (pintype "passive"))
    )
    (net (code "60") (name "Net-(IC2B-I1)") (class "Default")
      (node (ref "C11") (pin "2") (pinfunction "2_2") (pintype "passive"))
      (node (ref "IC2") (pin "5") (pinfunction "I1_5") (pintype "input"))
    )
    (net (code "61") (name "Net-(IC2B-O)") (class "Default")
      (node (ref "IC2") (pin "6") (pinfunction "O_6") (pintype "output"))
      (node (ref "OK11") (pin "1") (pinfunction "A_1") (pintype "passive"))
      (node (ref "RN4") (pin "3") (pinfunction "2_3") (pintype "passive"))
    )
    (net (code "62") (name "Net-(IC2C-I1)") (class "Default")
      (node (ref "C12") (pin "2") (pinfunction "2_2") (pintype "passive"))
      (node (ref "IC2") (pin "9") (pinfunction "I1_9") (pintype "input"))
    )
    (net (code "63") (name "Net-(IC2C-O)") (class "Default")
      (node (ref "IC2") (pin "8") (pinfunction "O_8") (pintype "output"))
      (node (ref "OK12") (pin "1") (pinfunction "A_1") (pintype "passive"))
      (node (ref "RN4") (pin "4") (pinfunction "2_4") (pintype "passive"))
    )
    (net (code "64") (name "Net-(IC2D-I1)") (class "Default")
      (node (ref "C16") (pin "2") (pinfunction "2_2") (pintype "passive"))
      (node (ref "IC2") (pin "12") (pinfunction "I1_12") (pintype "input"))
    )
    (net (code "65") (name "Net-(IC2D-O)") (class "Default")
      (node (ref "IC2") (pin "11") (pinfunction "O_11") (pintype "output"))
      (node (ref "OK13") (pin "1") (pinfunction "A_1") (pintype "passive"))
      (node (ref "RN4") (pin "5") (pinfunction "2_5") (pintype "passive"))
    )
    (net (code "66") (name "Net-(IC3A-I1)") (class "Default")
      (node (ref "C1") (pin "2") (pinfunction "2_2") (pintype "passive"))
      (node (ref "IC3") (pin "2") (pinfunction "I1_2") (pintype "input"))
    )
    (net (code "67") (name "Net-(IC3A-O)") (class "Default")
      (node (ref "IC3") (pin "3") (pinfunction "O_3") (pintype "output"))
      (node (ref "OK15") (pin "1") (pinfunction "A_1") (pintype "passive"))
      (node (ref "RN4") (pin "7") (pinfunction "2_7") (pintype "passive"))
    )
    (net (code "68") (name "Net-(IC3B-I1)") (class "Default")
      (node (ref "C17") (pin "2") (pinfunction "2_2") (pintype "passive"))
      (node (ref "IC3") (pin "5") (pinfunction "I1_5") (pintype "input"))
    )
    (net (code "69") (name "Net-(IC3B-O)") (class "Default")
      (node (ref "IC3") (pin "6") (pinfunction "O_6") (pintype "output"))
      (node (ref "OK14") (pin "1") (pinfunction "A_1") (pintype "passive"))
      (node (ref "RN4") (pin "6") (pinfunction "2_6") (pintype "passive"))
    )
    (net (code "70") (name "Net-(IC3C-I1)") (class "Default")
      (node (ref "C9") (pin "2") (pinfunction "2_2") (pintype "passive"))
      (node (ref "IC3") (pin "9") (pinfunction "I1_9") (pintype "input"))
    )
    (net (code "71") (name "Net-(IC3C-O)") (class "Default")
      (node (ref "IC3") (pin "8") (pinfunction "O_8") (pintype "output"))
      (node (ref "OK16") (pin "1") (pinfunction "A_1") (pintype "passive"))
      (node (ref "RN4") (pin "8") (pinfunction "2_8") (pintype "passive"))
    )
    (net (code "72") (name "Net-(IC3D-I1)") (class "Default")
      (node (ref "C18") (pin "2") (pinfunction "2_2") (pintype "passive"))
      (node (ref "IC3") (pin "12") (pinfunction "I1_12") (pintype "input"))
    )
    (net (code "73") (name "Net-(IC3D-O)") (class "Default")
      (node (ref "IC3") (pin "11") (pinfunction "O_11") (pintype "output"))
      (node (ref "OK17") (pin "1") (pinfunction "A_1") (pintype "passive"))
      (node (ref "RN4") (pin "9") (pinfunction "2_9") (pintype "passive"))
    )
    (net (code "74") (name "Net-(NENAB-1)") (class "Default")
      (node (ref "NENA") (pin "2") (pinfunction "1_2") (pintype "passive"))
      (node (ref "R8") (pin "2") (pinfunction "2_2") (pintype "passive"))
    )
    (net (code "75") (name "Net-(OFF-C)") (class "Default")
      (node (ref "OFF") (pin "K") (pinfunction "C_K") (pintype "passive"))
      (node (ref "R2") (pin "2") (pinfunction "2_2") (pintype "passive"))
    )
    (net (code "76") (name "Net-(OK-SIG-AC1)") (class "Default")
      (node (ref "OK-SIG") (pin "1") (pinfunction "AC1_1") (pintype "passive"))
      (node (ref "R/C2") (pin "1") (pinfunction "1_1") (pintype "passive"))
    )
    (net (code "77") (name "Net-(OK-SIG-AC2)") (class "Default")
      (node (ref "OK-SIG") (pin "2") (pinfunction "AC2_2") (pintype "passive"))
      (node (ref "R/C1") (pin "1") (pinfunction "1_1") (pintype "passive"))
    )
    (net (code "78") (name "Net-(OK-SIG-C)") (class "Default")
      (node (ref "C21") (pin "+") (pinfunction "+_+") (pintype "passive"))
      (node (ref "OK-SIG") (pin "4") (pinfunction "C_4") (pintype "passive"))
      (node (ref "R1") (pin "1") (pinfunction "1_1") (pintype "passive"))
      (node (ref "T2") (pin "2") (pinfunction "B_2") (pintype "passive"))
    )
    (net (code "79") (name "Net-(OK-SIG1-AC1)") (class "Default")
      (node (ref "OK-SIG1") (pin "1") (pinfunction "AC1_1") (pintype "passive"))
      (node (ref "R8") (pin "1") (pinfunction "1_1") (pintype "passive"))
    )
    (net (code "80") (name "Net-(OK-SIG1-AC2)") (class "Default")
      (node (ref "NENA") (pin "1") (pinfunction "1_1") (pintype "passive"))
      (node (ref "OK-SIG1") (pin "2") (pinfunction "AC2_2") (pintype "passive"))
    )
    (net (code "81") (name "Net-(OKP2-A)") (class "Default")
      (node (ref "OKP2") (pin "2") (pinfunction "A_2") (pintype "passive"))
      (node (ref "RN1") (pin "9") (pinfunction "2_9") (pintype "passive"))
    )
    (net (code "82") (name "Net-(OKP3-A)") (class "Default")
      (node (ref "OKP3") (pin "2") (pinfunction "A_2") (pintype "passive"))
      (node (ref "RN1") (pin "8") (pinfunction "2_8") (pintype "passive"))
    )
    (net (code "83") (name "Net-(OKP4-A)") (class "Default")
      (node (ref "OKP4") (pin "2") (pinfunction "A_2") (pintype "passive"))
      (node (ref "RN1") (pin "7") (pinfunction "2_7") (pintype "passive"))
    )
    (net (code "84") (name "Net-(OKP5-A)") (class "Default")
      (node (ref "OKP5") (pin "2") (pinfunction "A_2") (pintype "passive"))
      (node (ref "RN1") (pin "6") (pinfunction "2_6") (pintype "passive"))
    )
    (net (code "85") (name "Net-(OKP6-A)") (class "Default")
      (node (ref "OKP6") (pin "2") (pinfunction "A_2") (pintype "passive"))
      (node (ref "RN1") (pin "5") (pinfunction "2_5") (pintype "passive"))
    )
    (net (code "86") (name "Net-(OKP7-A)") (class "Default")
      (node (ref "OKP7") (pin "2") (pinfunction "A_2") (pintype "passive"))
      (node (ref "RN1") (pin "4") (pinfunction "2_4") (pintype "passive"))
    )
    (net (code "87") (name "Net-(OKP8-A)") (class "Default")
      (node (ref "OKP8") (pin "2") (pinfunction "A_2") (pintype "passive"))
      (node (ref "RN1") (pin "3") (pinfunction "2_3") (pintype "passive"))
    )
    (net (code "88") (name "Net-(OKP9-A)") (class "Default")
      (node (ref "OKP9") (pin "2") (pinfunction "A_2") (pintype "passive"))
      (node (ref "RN1") (pin "2") (pinfunction "2_2") (pintype "passive"))
    )
    (net (code "89") (name "Net-(P1-C)") (class "Default")
      (node (ref "P1") (pin "K") (pinfunction "C_K") (pintype "passive"))
      (node (ref "R7") (pin "2") (pinfunction "2_2") (pintype "passive"))
    )
    (net (code "90") (name "Net-(T1-E)") (class "Default")
      (node (ref "P1") (pin "A") (pinfunction "A_A") (pintype "passive"))
      (node (ref "T1") (pin "1") (pinfunction "E_1") (pintype "passive"))
    )
    (net (code "91") (name "Net-(VPC-C)") (class "Default")
      (node (ref "R21") (pin "2") (pinfunction "2_2") (pintype "passive"))
      (node (ref "VPC") (pin "K") (pinfunction "C_K") (pintype "passive"))
    )
    (net (code "92") (name "unconnected-(LPT-Pad26)") (class "Default")
      (node (ref "LPT") (pin "26") (pinfunction "26_26") (pintype "passive"))
    )
    (net (code "93") (name "unconnected-(X2-Pad2)") (class "Default")
      (node (ref "X2") (pin "2") (pinfunction "2_2") (pintype "passive"))
    )
    (net (code "94") (name "unconnected-(X2-Pad3)") (class "Default")
      (node (ref "X2") (pin "3") (pinfunction "3_3") (pintype "passive"))
    )
  )
)
